# Automated_Plant_Watering_System_Schemati.net
KiCad netlist of a schematic drawn in Altium Designer
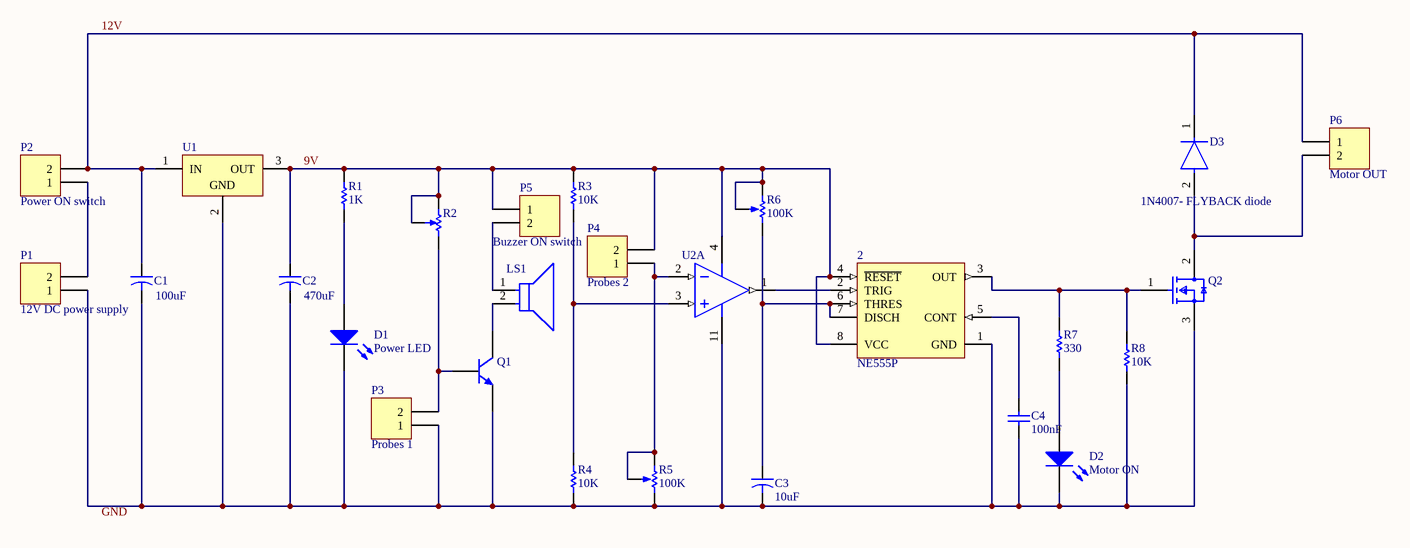
[diagram p0: Automated Plant Watering System Schematic.SchDoc]

(export (version "E")
  (design (tool "Eeschema 10.0.6"))
  (components
    (comp (ref "2")
      (value "NE555P")
      (footprint "P0008A")
      (description "IC OSC SINGLE TIMER 100KHZ 8-DIP")
      (libsource (lib "University of Moratuwa") (part "TI-NE555-P8"))
    )
    (comp (ref "C1")
      (value "100uF")
      (footprint "CAPR5-4X5")
      (description "Capacitor")
      (fields (field (name "PUBLISHER") "Altium Limited"))
      (libsource (lib "Miscellaneous Devices") (part "Cap2"))
    )
    (comp (ref "C2")
      (value "470uF")
      (footprint "CAPR5-4X5")
      (description "Capacitor")
      (fields (field (name "PUBLISHER") "Altium Limited"))
      (libsource (lib "Miscellaneous Devices") (part "Cap2"))
    )
    (comp (ref "C3")
      (value "10uF")
      (footprint "CAPR5-4X5")
      (description "Capacitor")
      (fields (field (name "PUBLISHER") "Altium Limited"))
      (libsource (lib "Miscellaneous Devices") (part "Cap2"))
    )
    (comp (ref "C4")
      (value "100nF")
      (footprint "RAD-0.3")
      (description "Capacitor")
      (fields (field (name "PUBLISHER") "Altium Limited"))
      (libsource (lib "Miscellaneous Devices") (part "Cap"))
    )
    (comp (ref "D1")
      (value "Power LED")
      (footprint "LED-1")
      (description "Typical RED GaAs LED")
      (fields (field (name "PUBLISHER") "Altium Limited"))
      (libsource (lib "Miscellaneous Devices") (part "LED1"))
    )
    (comp (ref "D2")
      (value "Motor ON")
      (footprint "LED-1")
      (description "Typical RED GaAs LED")
      (fields (field (name "PUBLISHER") "Altium Limited"))
      (libsource (lib "Miscellaneous Devices") (part "LED1"))
    )
    (comp (ref "D3")
      (value "1N4007- FLYBACK diode")
      (footprint "FP-1N4007-MFG")
      (description "DIODE GEN PURP 1KV 1A DO204AL")
      (fields
        (field (name "OCTOPART") "https://octopart.com/1n4007-e3%2F54-vishay-39548207")
        (field (name "MANUFACTURER") "Vishay")
      )
      (libsource (lib "Altium Content Vault") (part "d7152d700b627762746794eb795d46e"))
    )
    (comp (ref "LS1")
      (value "AI-1223-TWT-5V-R")
      (footprint "FP-AI-1223-TWT-5V-R-MFG")
      (description "AUDIO MAGNETIC INDICATOR 3-7V TH")
      (libsource (lib "Altium Content Vault") (part "1973c4b650225fd2ddacaff6b763965"))
    )
    (comp (ref "P1")
      (value "12V DC power supply")
      (footprint "HDR1X2")
      (description "Header, 2-Pin")
      (fields (field (name "PUBLISHER") "Altium Limited"))
      (libsource (lib "Miscellaneous Connectors") (part "Header 2"))
    )
    (comp (ref "P2")
      (value "Power ON switch")
      (footprint "HDR1X2")
      (description "Header, 2-Pin")
      (fields (field (name "PUBLISHER") "Altium Limited"))
      (libsource (lib "Miscellaneous Connectors") (part "Header 2"))
    )
    (comp (ref "P3")
      (value "Probes 1")
      (footprint "HDR1X2")
      (description "Header, 2-Pin")
      (fields (field (name "PUBLISHER") "Altium Limited"))
      (libsource (lib "Miscellaneous Connectors") (part "Header 2"))
    )
    (comp (ref "P4")
      (value "Probes 2")
      (footprint "HDR1X2")
      (description "Header, 2-Pin")
      (fields (field (name "PUBLISHER") "Altium Limited"))
      (libsource (lib "Miscellaneous Connectors") (part "Header 2"))
    )
    (comp (ref "P5")
      (value "Buzzer ON switch")
      (footprint "HDR1X2")
      (description "Header, 2-Pin")
      (fields (field (name "PUBLISHER") "Altium Limited"))
      (libsource (lib "") (part "Header 2_1"))
    )
    (comp (ref "P6")
      (value "Motor OUT")
      (footprint "HDR1X2")
      (description "Header, 2-Pin")
      (fields (field (name "PUBLISHER") "Altium Limited"))
      (libsource (lib "") (part "Header 2_1"))
    )
    (comp (ref "Q1")
      (value "NPN")
      (footprint "TO-226-AA")
      (description "NPN Bipolar Transistor")
      (fields (field (name "PUBLISHER") "Altium Limited"))
      (libsource (lib "Miscellaneous Devices") (part "NPN"))
    )
    (comp (ref "Q2")
      (value "FQP30N06")
      (footprint "FP-340AT-MFG")
      (description "Power MOSFET, N-Channel, QFET®, 60 V, 30 A, 40 mΩ, TO-220")
      (libsource (lib "University of Moratuwa") (part "b44c8776e10362b01251f5cff19d373"))
    )
    (comp (ref "R1")
      (value "1K")
      (footprint "AXIAL-0.3")
      (description "Resistor")
      (fields (field (name "PUBLISHER") "Altium Limited"))
      (libsource (lib "Miscellaneous Devices") (part "Res1"))
    )
    (comp (ref "R2")
      (value "93PR1KLF")
      (footprint "BIT-93PR1KLF")
      (fields (field (name "MANUFACTURER") "BI Technologies"))
      (libsource (lib "Altium Content Vault") (part "RES-ADJ-3_A"))
    )
    (comp (ref "R3")
      (value "10K")
      (footprint "AXIAL-0.3")
      (description "Resistor")
      (fields (field (name "PUBLISHER") "Altium Limited"))
      (libsource (lib "Miscellaneous Devices") (part "Res1"))
    )
    (comp (ref "R4")
      (value "10K")
      (footprint "AXIAL-0.3")
      (description "Resistor")
      (fields (field (name "PUBLISHER") "Altium Limited"))
      (libsource (lib "Miscellaneous Devices") (part "Res1"))
    )
    (comp (ref "R5")
      (value "100K")
      (footprint "VR5")
      (description "Potentiometer")
      (fields (field (name "PUBLISHER") "Altium Limited"))
      (libsource (lib "Miscellaneous Devices") (part "RPot"))
    )
    (comp (ref "R6")
      (value "100K")
      (footprint "VR5")
      (description "Potentiometer")
      (fields (field (name "PUBLISHER") "Altium Limited"))
      (libsource (lib "Miscellaneous Devices") (part "RPot"))
    )
    (comp (ref "R7")
      (value "330")
      (footprint "AXIAL-0.3")
      (description "Resistor")
      (fields (field (name "PUBLISHER") "Altium Limited"))
      (libsource (lib "Miscellaneous Devices") (part "Res1"))
    )
    (comp (ref "R8")
      (value "10K")
      (footprint "AXIAL-0.3")
      (description "Resistor")
      (fields (field (name "PUBLISHER") "Altium Limited"))
      (libsource (lib "Miscellaneous Devices") (part "Res1"))
    )
    (comp (ref "U1")
      (value "L7809CV")
      (footprint "TO220")
      (description "IC REG LDO 9V 1.5A TO220AB")
      (libsource (lib "University of Moratuwa") (part "PM-REG-L4940-SIL3"))
    )
    (comp (ref "U2")
      (value "LM324AN")
      (footprint "N0014A")
      (description "Quadruple improved offset operational amplifier 14-PDIP 0 to 70")
      (libsource (lib "University of Moratuwa") (part "AMP-OPA-LM124-14"))
    )
  )
  (nets
    (net (code "1") (name "/9V") (class "Default")
      (node (ref "2") (pin "4") (pinfunction "~{RESET}_4") (pintype "input"))
      (node (ref "2") (pin "8") (pinfunction "VCC_8") (pintype "power_in"))
      (node (ref "C2") (pin "1") (pinfunction "1_1") (pintype "passive"))
      (node (ref "P4") (pin "2") (pinfunction "2_2") (pintype "passive"))
      (node (ref "P5") (pin "1") (pinfunction "1_1") (pintype "passive"))
      (node (ref "R1") (pin "2") (pinfunction "2_2") (pintype "passive"))
      (node (ref "R2") (pin "1") (pinfunction "1_1") (pintype "passive"))
      (node (ref "R2") (pin "2") (pinfunction "2_2") (pintype "passive"))
      (node (ref "R3") (pin "2") (pinfunction "2_2") (pintype "passive"))
      (node (ref "R6") (pin "1") (pinfunction "TOP_1") (pintype "passive"))
      (node (ref "R6") (pin "3") (pinfunction "TAP_3") (pintype "passive"))
      (node (ref "U1") (pin "3") (pinfunction "OUT_3") (pintype "power_in"))
      (node (ref "U2") (pin "4") (pinfunction "V+_4") (pintype "power_in"))
    )
    (net (code "2") (name "/12V") (class "Default")
      (node (ref "C1") (pin "1") (pinfunction "1_1") (pintype "passive"))
      (node (ref "D3") (pin "1") (pinfunction "C_1") (pintype "passive"))
      (node (ref "P2") (pin "2") (pinfunction "2_2") (pintype "passive"))
      (node (ref "P6") (pin "1") (pinfunction "1_1") (pintype "passive"))
      (node (ref "U1") (pin "1") (pinfunction "IN_1") (pintype "power_in"))
    )
    (net (code "4") (name "Net-(2-CONT)") (class "Default")
      (node (ref "2") (pin "5") (pinfunction "CONT_5") (pintype "input"))
      (node (ref "C4") (pin "2") (pinfunction "2_2") (pintype "passive"))
    )
    (net (code "5") (name "Net-(2-DISCH)") (class "Default")
      (node (ref "2") (pin "6") (pinfunction "THRES_6") (pintype "input"))
      (node (ref "2") (pin "7") (pinfunction "DISCH_7") (pintype "open_collector"))
      (node (ref "C3") (pin "1") (pinfunction "1_1") (pintype "passive"))
      (node (ref "R6") (pin "2") (pinfunction "BOT_2") (pintype "passive"))
    )
    (net (code "6") (name "Net-(2-GND)") (class "Default")
      (node (ref "2") (pin "1") (pinfunction "GND_1") (pintype "power_in"))
      (node (ref "C1") (pin "2") (pinfunction "2_2") (pintype "passive"))
      (node (ref "C2") (pin "2") (pinfunction "2_2") (pintype "passive"))
      (node (ref "C3") (pin "2") (pinfunction "2_2") (pintype "passive"))
      (node (ref "C4") (pin "1") (pinfunction "1_1") (pintype "passive"))
      (node (ref "D1") (pin "2") (pinfunction "K_2") (pintype "passive"))
      (node (ref "D2") (pin "2") (pinfunction "K_2") (pintype "passive"))
      (node (ref "P1") (pin "1") (pinfunction "1_1") (pintype "passive"))
      (node (ref "P3") (pin "1") (pinfunction "1_1") (pintype "passive"))
      (node (ref "Q1") (pin "3") (pinfunction "E_3") (pintype "passive"))
      (node (ref "Q2") (pin "3") (pinfunction "S_3") (pintype "passive"))
      (node (ref "R4") (pin "1") (pinfunction "1_1") (pintype "passive"))
      (node (ref "R5") (pin "2") (pinfunction "BOT_2") (pintype "passive"))
      (node (ref "R8") (pin "1") (pinfunction "1_1") (pintype "passive"))
      (node (ref "U1") (pin "2") (pinfunction "GND_2") (pintype "power_in"))
      (node (ref "U2") (pin "11") (pinfunction "GND_11") (pintype "power_in"))
    )
    (net (code "7") (name "Net-(2-OUT)") (class "Default")
      (node (ref "2") (pin "3") (pinfunction "OUT_3") (pintype "output"))
      (node (ref "Q2") (pin "1") (pinfunction "G_1") (pintype "passive"))
      (node (ref "R7") (pin "2") (pinfunction "2_2") (pintype "passive"))
      (node (ref "R8") (pin "2") (pinfunction "2_2") (pintype "passive"))
    )
    (net (code "8") (name "Net-(2-TRIG)") (class "Default")
      (node (ref "2") (pin "2") (pinfunction "TRIG_2") (pintype "input"))
      (node (ref "U2") (pin "1") (pinfunction "OUT1_1") (pintype "output"))
    )
    (net (code "9") (name "Net-(D1-A)") (class "Default")
      (node (ref "D1") (pin "1") (pinfunction "A_1") (pintype "passive"))
      (node (ref "R1") (pin "1") (pinfunction "1_1") (pintype "passive"))
    )
    (net (code "10") (name "Net-(D2-A)") (class "Default")
      (node (ref "D2") (pin "1") (pinfunction "A_1") (pintype "passive"))
      (node (ref "R7") (pin "1") (pinfunction "1_1") (pintype "passive"))
    )
    (net (code "11") (name "Net-(D3-A)") (class "Default")
      (node (ref "D3") (pin "2") (pinfunction "A_2") (pintype "passive"))
      (node (ref "P6") (pin "2") (pinfunction "2_2") (pintype "passive"))
      (node (ref "Q2") (pin "2") (pinfunction "D_2") (pintype "passive"))
    )
    (net (code "12") (name "Net-(LS1-A)") (class "Default")
      (node (ref "LS1") (pin "2") (pinfunction "A_2") (pintype "passive"))
      (node (ref "Q1") (pin "1") (pinfunction "C_1") (pintype "passive"))
    )
    (net (code "13") (name "Net-(LS1-C)") (class "Default")
      (node (ref "LS1") (pin "1") (pinfunction "C_1") (pintype "passive"))
      (node (ref "P5") (pin "2") (pinfunction "2_2") (pintype "passive"))
    )
    (net (code "14") (name "Net-(P1-Pad2)") (class "Default")
      (node (ref "P1") (pin "2") (pinfunction "2_2") (pintype "passive"))
      (node (ref "P2") (pin "1") (pinfunction "1_1") (pintype "passive"))
    )
    (net (code "15") (name "Net-(Q1-B)") (class "Default")
      (node (ref "P3") (pin "2") (pinfunction "2_2") (pintype "passive"))
      (node (ref "Q1") (pin "2") (pinfunction "B_2") (pintype "passive"))
      (node (ref "R2") (pin "3") (pinfunction "3_3") (pintype "passive"))
    )
    (net (code "16") (name "Net-(R5-TAP)") (class "Default")
      (node (ref "P4") (pin "1") (pinfunction "1_1") (pintype "passive"))
      (node (ref "R5") (pin "1") (pinfunction "TOP_1") (pintype "passive"))
      (node (ref "R5") (pin "3") (pinfunction "TAP_3") (pintype "passive"))
      (node (ref "U2") (pin "2") (pinfunction "IN1-_2") (pintype "input"))
    )
    (net (code "17") (name "Net-(U2A-IN1+)") (class "Default")
      (node (ref "R3") (pin "1") (pinfunction "1_1") (pintype "passive"))
      (node (ref "R4") (pin "2") (pinfunction "2_2") (pintype "passive"))
      (node (ref "U2") (pin "3") (pinfunction "IN1+_3") (pintype "input"))
    )
  )
)
